# supra_redraw.net
KiCad netlist of a schematic drawn in EAGLE
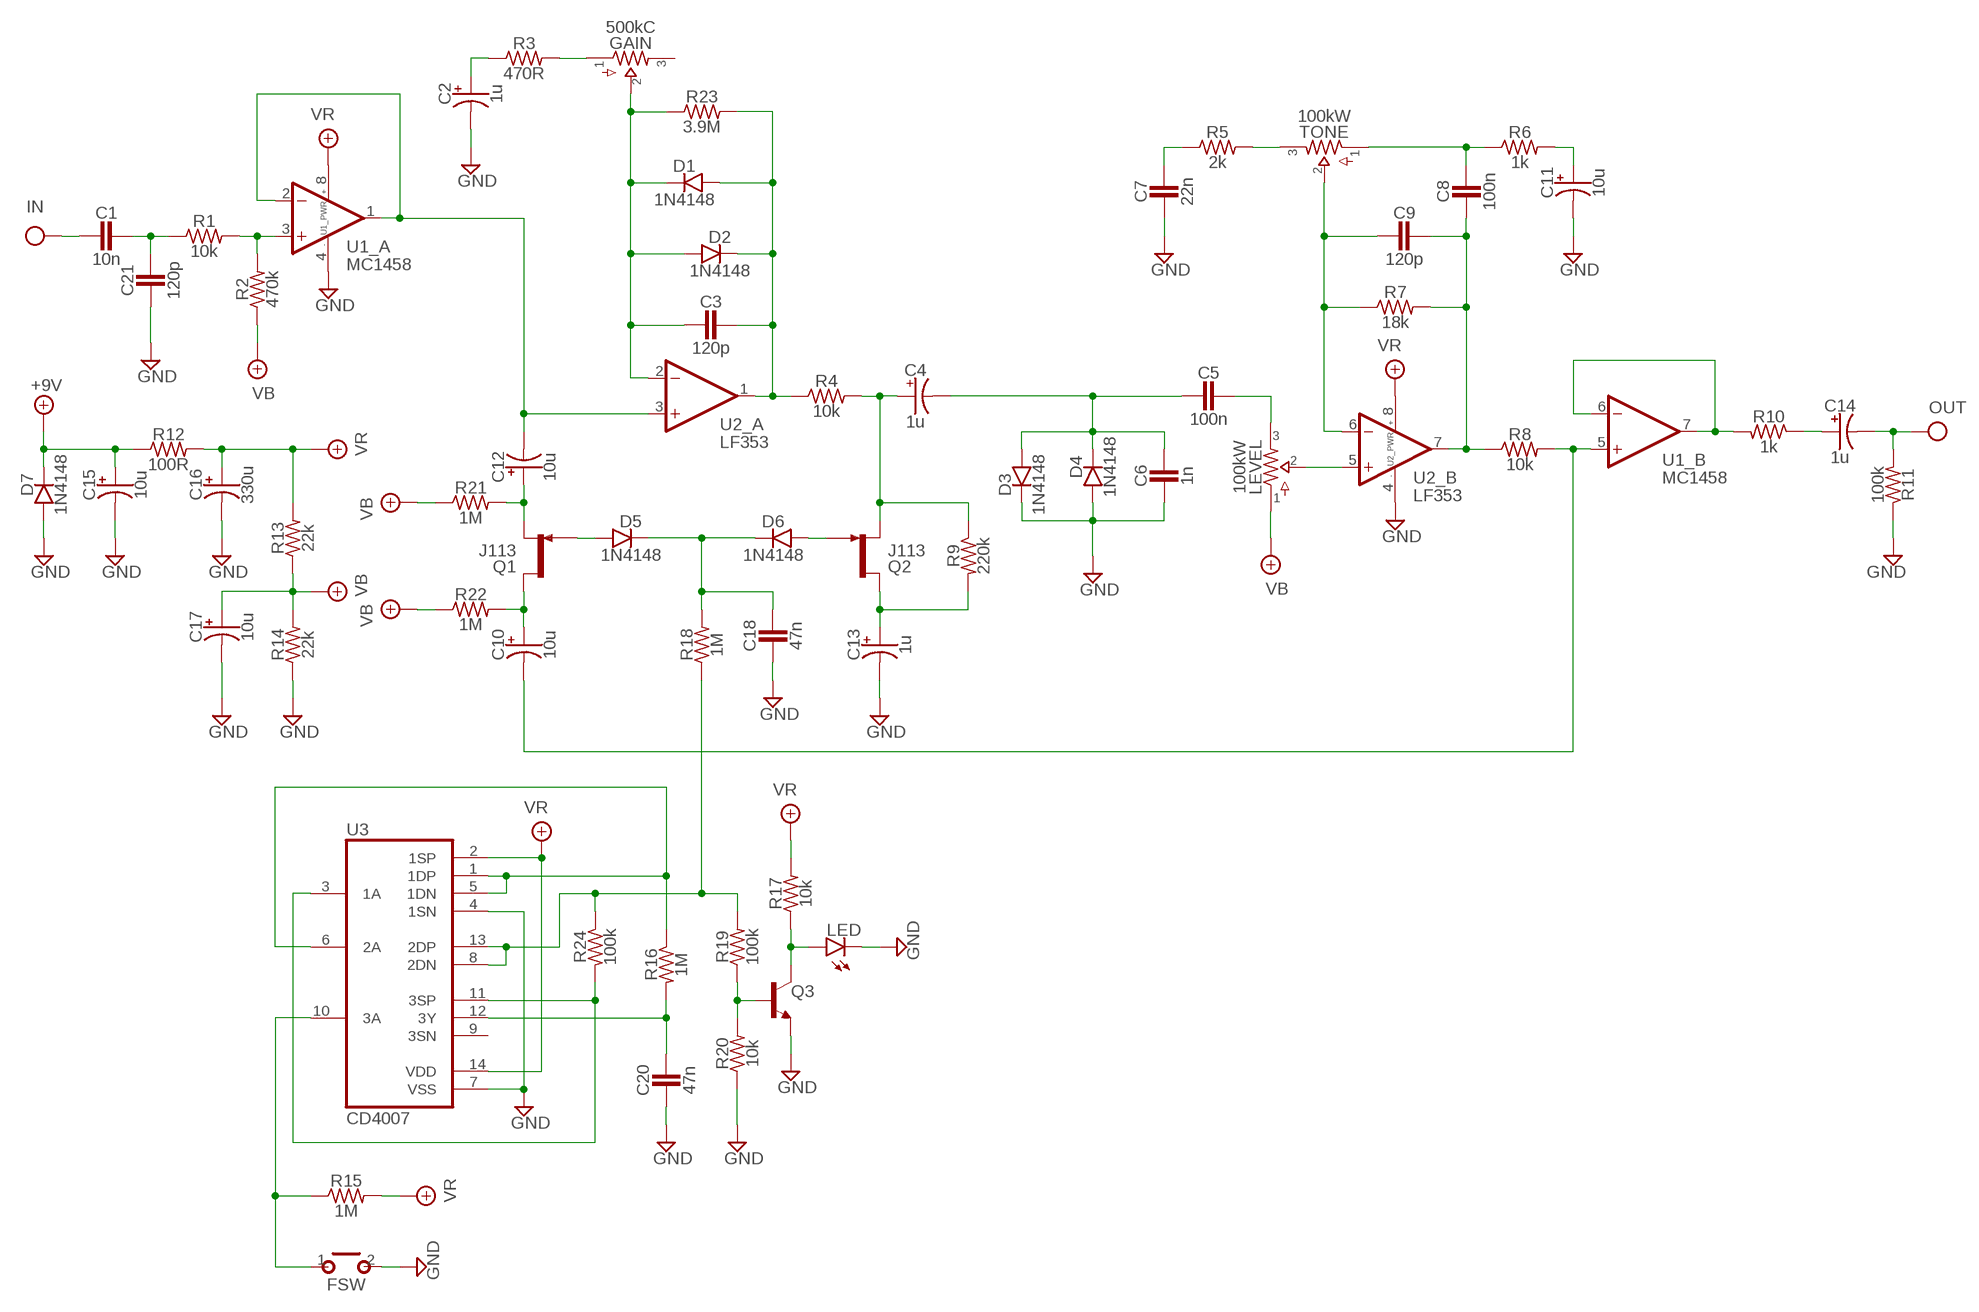
[diagram p0: schematic, sheet 1]

(export (version "E")
  (design (tool "Eeschema 10.0.6"))
  (components
    (comp (ref "C1")
      (value "10n")
      (footprint "eagle-import:BOX_SMALL")
      (libsource (lib "eagle-import") (part "CER/FILMBOX.1"))
    )
    (comp (ref "C2")
      (value "1u")
      (footprint "eagle-import:050_020")
      (libsource (lib "eagle-import") (part "0500"))
    )
    (comp (ref "C3")
      (value "120p")
      (footprint "eagle-import:BOX_SMALL")
      (libsource (lib "eagle-import") (part "CER/FILMBOX.1"))
    )
    (comp (ref "C4")
      (value "1u")
      (footprint "eagle-import:050_020")
      (libsource (lib "eagle-import") (part "0500"))
    )
    (comp (ref "C5")
      (value "100n")
      (footprint "eagle-import:BOX_SMALL")
      (libsource (lib "eagle-import") (part "CER/FILMBOX.1"))
    )
    (comp (ref "C6")
      (value "1n")
      (footprint "eagle-import:BOX_SMALL")
      (libsource (lib "eagle-import") (part "CER/FILMBOX.1"))
    )
    (comp (ref "C7")
      (value "22n")
      (footprint "eagle-import:BOX_SMALL")
      (libsource (lib "eagle-import") (part "CER/FILMBOX.1"))
    )
    (comp (ref "C8")
      (value "100n")
      (footprint "eagle-import:BOX_SMALL")
      (libsource (lib "eagle-import") (part "CER/FILMBOX.1"))
    )
    (comp (ref "C9")
      (value "120p")
      (footprint "eagle-import:BOX_SMALL")
      (libsource (lib "eagle-import") (part "CER/FILMBOX.1"))
    )
    (comp (ref "C10")
      (value "10u")
      (footprint "eagle-import:050_020")
      (libsource (lib "eagle-import") (part "0500"))
    )
    (comp (ref "C11")
      (value "10u")
      (footprint "eagle-import:050_020")
      (libsource (lib "eagle-import") (part "0500"))
    )
    (comp (ref "C12")
      (value "10u")
      (footprint "eagle-import:050_020")
      (libsource (lib "eagle-import") (part "0500"))
    )
    (comp (ref "C13")
      (value "1u")
      (footprint "eagle-import:050_020")
      (libsource (lib "eagle-import") (part "0500"))
    )
    (comp (ref "C14")
      (value "1u")
      (footprint "eagle-import:050_020")
      (libsource (lib "eagle-import") (part "0500"))
    )
    (comp (ref "C15")
      (value "10u")
      (footprint "eagle-import:050_020")
      (libsource (lib "eagle-import") (part "0500"))
    )
    (comp (ref "C16")
      (value "330u")
      (footprint "eagle-import:050_020")
      (libsource (lib "eagle-import") (part "0500"))
    )
    (comp (ref "C17")
      (value "10u")
      (footprint "eagle-import:050_020")
      (libsource (lib "eagle-import") (part "0500"))
    )
    (comp (ref "C18")
      (value "47n")
      (footprint "eagle-import:BOX_SMALL")
      (libsource (lib "eagle-import") (part "CER/FILMBOX.1"))
    )
    (comp (ref "C20")
      (value "47n")
      (footprint "eagle-import:BOX_SMALL")
      (libsource (lib "eagle-import") (part "CER/FILMBOX.1"))
    )
    (comp (ref "C21")
      (value "120p")
      (footprint "eagle-import:BOX_SMALL")
      (libsource (lib "eagle-import") (part "CER/FILMBOX.1"))
    )
    (comp (ref "D1")
      (value "1N4148")
      (footprint "eagle-import:DO35-2")
      (libsource (lib "eagle-import") (part "DO35.2"))
    )
    (comp (ref "D2")
      (value "1N4148")
      (footprint "eagle-import:DO35-2")
      (libsource (lib "eagle-import") (part "DO35.2"))
    )
    (comp (ref "D3")
      (value "1N4148")
      (footprint "eagle-import:DO35-2")
      (libsource (lib "eagle-import") (part "DO35.2"))
    )
    (comp (ref "D4")
      (value "1N4148")
      (footprint "eagle-import:DO35-2")
      (libsource (lib "eagle-import") (part "DO35.2"))
    )
    (comp (ref "D5")
      (value "1N4148")
      (footprint "eagle-import:DO35-2")
      (libsource (lib "eagle-import") (part "DO35.2"))
    )
    (comp (ref "D6")
      (value "1N4148")
      (footprint "eagle-import:DO35-2")
      (libsource (lib "eagle-import") (part "DO35.2"))
    )
    (comp (ref "D7")
      (value "1N4148")
      (footprint "eagle-import:DO35-2")
      (libsource (lib "eagle-import") (part "DO35.2"))
    )
    (comp (ref "FSW")
      (value "MOMENTARY")
      (footprint "eagle-import:SPST")
      (libsource (lib "eagle-import") (part "MOMENTARY"))
    )
    (comp (ref "GAIN")
      (value "500kC")
      (footprint "eagle-import:16MM")
      (libsource (lib "eagle-import") (part "POTS16MM"))
    )
    (comp (ref "LED")
      (value "LED")
      (footprint "eagle-import:3MM_D")
      (libsource (lib "eagle-import") (part "LED"))
    )
    (comp (ref "LEVEL")
      (value "100kW")
      (footprint "eagle-import:16MM")
      (libsource (lib "eagle-import") (part "POTS16MM"))
    )
    (comp (ref "Q1")
      (value "J113")
      (footprint "eagle-import:TO92-")
      (libsource (lib "eagle-import") (part "2N5457"))
    )
    (comp (ref "Q2")
      (value "J113")
      (footprint "eagle-import:TO92-")
      (libsource (lib "eagle-import") (part "2N5457"))
    )
    (comp (ref "Q3")
      (value "2N3904")
      (footprint "eagle-import:TO92-")
      (libsource (lib "eagle-import") (part "2N3904"))
    )
    (comp (ref "R1")
      (value "10k")
      (footprint "eagle-import:R0207_3")
      (libsource (lib "eagle-import") (part "R_.3B"))
    )
    (comp (ref "R2")
      (value "470k")
      (footprint "eagle-import:R0207_3")
      (libsource (lib "eagle-import") (part "R_.3B"))
    )
    (comp (ref "R3")
      (value "470R")
      (footprint "eagle-import:R0207_3")
      (libsource (lib "eagle-import") (part "R_.3B"))
    )
    (comp (ref "R4")
      (value "10k")
      (footprint "eagle-import:R0207_3")
      (libsource (lib "eagle-import") (part "R_.3B"))
    )
    (comp (ref "R5")
      (value "2k")
      (footprint "eagle-import:R0207_3")
      (libsource (lib "eagle-import") (part "R_.3B"))
    )
    (comp (ref "R6")
      (value "1k")
      (footprint "eagle-import:R0207_3")
      (libsource (lib "eagle-import") (part "R_.3B"))
    )
    (comp (ref "R7")
      (value "18k")
      (footprint "eagle-import:R0207_3")
      (libsource (lib "eagle-import") (part "R_.3B"))
    )
    (comp (ref "R8")
      (value "10k")
      (footprint "eagle-import:R0207_3")
      (libsource (lib "eagle-import") (part "R_.3B"))
    )
    (comp (ref "R9")
      (value "220k")
      (footprint "eagle-import:R0207_3")
      (libsource (lib "eagle-import") (part "R_.3B"))
    )
    (comp (ref "R10")
      (value "1k")
      (footprint "eagle-import:R0207_3")
      (libsource (lib "eagle-import") (part "R_.3B"))
    )
    (comp (ref "R11")
      (value "100k")
      (footprint "eagle-import:R0207_3")
      (libsource (lib "eagle-import") (part "R_.3B"))
    )
    (comp (ref "R12")
      (value "100R")
      (footprint "eagle-import:R0207_3")
      (libsource (lib "eagle-import") (part "R_.3B"))
    )
    (comp (ref "R13")
      (value "22k")
      (footprint "eagle-import:R0207_3")
      (libsource (lib "eagle-import") (part "R_.3B"))
    )
    (comp (ref "R14")
      (value "22k")
      (footprint "eagle-import:R0207_3")
      (libsource (lib "eagle-import") (part "R_.3B"))
    )
    (comp (ref "R15")
      (value "1M")
      (footprint "eagle-import:R0207_3")
      (libsource (lib "eagle-import") (part "R_.3B"))
    )
    (comp (ref "R16")
      (value "1M")
      (footprint "eagle-import:R0207_3")
      (libsource (lib "eagle-import") (part "R_.3B"))
    )
    (comp (ref "R17")
      (value "10k")
      (footprint "eagle-import:R0207_3")
      (libsource (lib "eagle-import") (part "R_.3B"))
    )
    (comp (ref "R18")
      (value "1M")
      (footprint "eagle-import:R0207_3")
      (libsource (lib "eagle-import") (part "R_.3B"))
    )
    (comp (ref "R19")
      (value "100k")
      (footprint "eagle-import:R0207_3")
      (libsource (lib "eagle-import") (part "R_.3B"))
    )
    (comp (ref "R20")
      (value "10k")
      (footprint "eagle-import:R0207_3")
      (libsource (lib "eagle-import") (part "R_.3B"))
    )
    (comp (ref "R21")
      (value "1M")
      (footprint "eagle-import:R0207_3")
      (libsource (lib "eagle-import") (part "R_.3B"))
    )
    (comp (ref "R22")
      (value "1M")
      (footprint "eagle-import:R0207_3")
      (libsource (lib "eagle-import") (part "R_.3B"))
    )
    (comp (ref "R23")
      (value "3.9M")
      (footprint "eagle-import:R0207_3")
      (libsource (lib "eagle-import") (part "R_.3B"))
    )
    (comp (ref "R24")
      (value "100k")
      (footprint "eagle-import:R0207_3")
      (libsource (lib "eagle-import") (part "R_.3B"))
    )
    (comp (ref "TONE")
      (value "100kW")
      (footprint "eagle-import:16MM")
      (libsource (lib "eagle-import") (part "POTS16MM"))
    )
    (comp (ref "U1")
      (value "MC1458")
      (footprint "eagle-import:DIL0")
      (libsource (lib "eagle-import") (part "DUALTH"))
    )
    (comp (ref "U2")
      (value "LF353")
      (footprint "eagle-import:DIL0")
      (libsource (lib "eagle-import") (part "DUALTH"))
    )
    (comp (ref "U3")
      (value "CD4007")
      (footprint "eagle-import:DIL14")
      (libsource (lib "eagle-import") (part "4007N"))
    )
  )
  (nets
    (net (code "1") (name "+9V") (class "Default")
      (node (ref "C15") (pin "+") (pinfunction "+_+") (pintype "passive"))
      (node (ref "D7") (pin "C") (pinfunction "C_C") (pintype "passive"))
      (node (ref "R12") (pin "1") (pinfunction "1_1") (pintype "passive"))
    )
    (net (code "2") (name "GND") (class "Default")
      (node (ref "C11") (pin "-") (pinfunction "-_-") (pintype "passive"))
      (node (ref "C13") (pin "-") (pinfunction "-_-") (pintype "passive"))
      (node (ref "C15") (pin "-") (pinfunction "-_-") (pintype "passive"))
      (node (ref "C16") (pin "-") (pinfunction "-_-") (pintype "passive"))
      (node (ref "C17") (pin "-") (pinfunction "-_-") (pintype "passive"))
      (node (ref "C18") (pin "2") (pinfunction "2_2") (pintype "passive"))
      (node (ref "C2") (pin "-") (pinfunction "-_-") (pintype "passive"))
      (node (ref "C20") (pin "2") (pinfunction "2_2") (pintype "passive"))
      (node (ref "C21") (pin "2") (pinfunction "2_2") (pintype "passive"))
      (node (ref "C6") (pin "2") (pinfunction "2_2") (pintype "passive"))
      (node (ref "C7") (pin "2") (pinfunction "2_2") (pintype "passive"))
      (node (ref "D3") (pin "C") (pinfunction "C_C") (pintype "passive"))
      (node (ref "D4") (pin "A") (pinfunction "A_A") (pintype "passive"))
      (node (ref "D7") (pin "A") (pinfunction "A_A") (pintype "passive"))
      (node (ref "FSW") (pin "2") (pinfunction "S_2") (pintype "passive"))
      (node (ref "LED") (pin "P$1") (pinfunction "C_P$1") (pintype "passive"))
      (node (ref "Q3") (pin "3") (pinfunction "E_3") (pintype "passive"))
      (node (ref "R11") (pin "1") (pinfunction "1_1") (pintype "passive"))
      (node (ref "R14") (pin "1") (pinfunction "1_1") (pintype "passive"))
      (node (ref "R20") (pin "1") (pinfunction "1_1") (pintype "passive"))
      (node (ref "U1") (pin "4") (pinfunction "V-_4") (pintype "power_in"))
      (node (ref "U2") (pin "4") (pinfunction "V-_4") (pintype "power_in"))
      (node (ref "U3") (pin "4") (pinfunction "1SN_4") (pintype "open_collector"))
      (node (ref "U3") (pin "7") (pinfunction "VSS_7") (pintype "input"))
    )
    (net (code "3") (name "IN") (class "Default")
      (node (ref "C1") (pin "2") (pinfunction "2_2") (pintype "passive"))
    )
    (net (code "4") (name "Net-(C1-Pad1)") (class "Default")
      (node (ref "C1") (pin "1") (pinfunction "1_1") (pintype "passive"))
      (node (ref "C21") (pin "1") (pinfunction "1_1") (pintype "passive"))
      (node (ref "R1") (pin "1") (pinfunction "1_1") (pintype "passive"))
    )
    (net (code "5") (name "Net-(C2-Pad+)") (class "Default")
      (node (ref "C2") (pin "+") (pinfunction "+_+") (pintype "passive"))
      (node (ref "R3") (pin "1") (pinfunction "1_1") (pintype "passive"))
    )
    (net (code "6") (name "Net-(C4-Pad-)") (class "Default")
      (node (ref "C4") (pin "-") (pinfunction "-_-") (pintype "passive"))
      (node (ref "C5") (pin "2") (pinfunction "2_2") (pintype "passive"))
      (node (ref "C6") (pin "1") (pinfunction "1_1") (pintype "passive"))
      (node (ref "D3") (pin "A") (pinfunction "A_A") (pintype "passive"))
      (node (ref "D4") (pin "C") (pinfunction "C_C") (pintype "passive"))
    )
    (net (code "7") (name "Net-(C5-Pad1)") (class "Default")
      (node (ref "C5") (pin "1") (pinfunction "1_1") (pintype "passive"))
      (node (ref "LEVEL") (pin "3") (pinfunction "3_3") (pintype "passive"))
    )
    (net (code "8") (name "Net-(C7-Pad1)") (class "Default")
      (node (ref "C7") (pin "1") (pinfunction "1_1") (pintype "passive"))
      (node (ref "R5") (pin "1") (pinfunction "1_1") (pintype "passive"))
    )
    (net (code "9") (name "Net-(C8-Pad1)") (class "Default")
      (node (ref "C8") (pin "1") (pinfunction "1_1") (pintype "passive"))
      (node (ref "R6") (pin "1") (pinfunction "1_1") (pintype "passive"))
      (node (ref "TONE") (pin "1") (pinfunction "1_1") (pintype "passive"))
    )
    (net (code "10") (name "Net-(C11-Pad+)") (class "Default")
      (node (ref "C11") (pin "+") (pinfunction "+_+") (pintype "passive"))
      (node (ref "R6") (pin "2") (pinfunction "2_2") (pintype "passive"))
    )
    (net (code "11") (name "Net-(C14-Pad+)") (class "Default")
      (node (ref "C14") (pin "+") (pinfunction "+_+") (pintype "passive"))
      (node (ref "R10") (pin "1") (pinfunction "1_1") (pintype "passive"))
    )
    (net (code "12") (name "Net-(C18-Pad1)") (class "Default")
      (node (ref "C18") (pin "1") (pinfunction "1_1") (pintype "passive"))
      (node (ref "D5") (pin "C") (pinfunction "C_C") (pintype "passive"))
      (node (ref "D6") (pin "C") (pinfunction "C_C") (pintype "passive"))
      (node (ref "R18") (pin "2") (pinfunction "2_2") (pintype "passive"))
    )
    (net (code "13") (name "Net-(FSW-P)") (class "Default")
      (node (ref "FSW") (pin "1") (pinfunction "P_1") (pintype "passive"))
      (node (ref "R15") (pin "1") (pinfunction "1_1") (pintype "passive"))
      (node (ref "U3") (pin "10") (pinfunction "3A_10") (pintype "input"))
    )
    (net (code "14") (name "Net-(GAIN-Pad1)") (class "Default")
      (node (ref "GAIN") (pin "1") (pinfunction "1_1") (pintype "passive"))
      (node (ref "R3") (pin "2") (pinfunction "2_2") (pintype "passive"))
    )
    (net (code "15") (name "Net-(LED-A)") (class "Default")
      (node (ref "LED") (pin "ANODE") (pinfunction "A_ANODE") (pintype "passive"))
      (node (ref "Q3") (pin "1") (pinfunction "C_1") (pintype "passive"))
      (node (ref "R17") (pin "1") (pinfunction "1_1") (pintype "passive"))
    )
    (net (code "16") (name "Net-(Q1-D)") (class "Default")
      (node (ref "C10") (pin "+") (pinfunction "+_+") (pintype "passive"))
      (node (ref "Q1") (pin "3") (pinfunction "D_3") (pintype "passive"))
      (node (ref "R22") (pin "2") (pinfunction "2_2") (pintype "passive"))
    )
    (net (code "17") (name "Net-(Q1-G)") (class "Default")
      (node (ref "D5") (pin "A") (pinfunction "A_A") (pintype "passive"))
      (node (ref "Q1") (pin "1") (pinfunction "G_1") (pintype "passive"))
    )
    (net (code "18") (name "Net-(Q1-S)") (class "Default")
      (node (ref "C12") (pin "+") (pinfunction "+_+") (pintype "passive"))
      (node (ref "Q1") (pin "2") (pinfunction "S_2") (pintype "passive"))
      (node (ref "R21") (pin "2") (pinfunction "2_2") (pintype "passive"))
    )
    (net (code "19") (name "Net-(Q2-D)") (class "Default")
      (node (ref "C13") (pin "+") (pinfunction "+_+") (pintype "passive"))
      (node (ref "Q2") (pin "3") (pinfunction "D_3") (pintype "passive"))
      (node (ref "R9") (pin "2") (pinfunction "2_2") (pintype "passive"))
    )
    (net (code "20") (name "Net-(Q2-G)") (class "Default")
      (node (ref "D6") (pin "A") (pinfunction "A_A") (pintype "passive"))
      (node (ref "Q2") (pin "1") (pinfunction "G_1") (pintype "passive"))
    )
    (net (code "21") (name "Net-(Q2-S)") (class "Default")
      (node (ref "C4") (pin "+") (pinfunction "+_+") (pintype "passive"))
      (node (ref "Q2") (pin "2") (pinfunction "S_2") (pintype "passive"))
      (node (ref "R4") (pin "2") (pinfunction "2_2") (pintype "passive"))
      (node (ref "R9") (pin "1") (pinfunction "1_1") (pintype "passive"))
    )
    (net (code "22") (name "Net-(Q3-B)") (class "Default")
      (node (ref "Q3") (pin "2") (pinfunction "B_2") (pintype "passive"))
      (node (ref "R19") (pin "1") (pinfunction "1_1") (pintype "passive"))
      (node (ref "R20") (pin "2") (pinfunction "2_2") (pintype "passive"))
    )
    (net (code "23") (name "Net-(R5-Pad2)") (class "Default")
      (node (ref "R5") (pin "2") (pinfunction "2_2") (pintype "passive"))
      (node (ref "TONE") (pin "3") (pinfunction "3_3") (pintype "passive"))
    )
    (net (code "24") (name "Net-(U1A-+IN)") (class "Default")
      (node (ref "R1") (pin "2") (pinfunction "2_2") (pintype "passive"))
      (node (ref "R2") (pin "2") (pinfunction "2_2") (pintype "passive"))
      (node (ref "U1") (pin "3") (pinfunction "+IN_3") (pintype "input"))
    )
    (net (code "25") (name "Net-(U1A--IN)") (class "Default")
      (node (ref "C12") (pin "-") (pinfunction "-_-") (pintype "passive"))
      (node (ref "U1") (pin "1") (pinfunction "OUT_1") (pintype "output"))
      (node (ref "U1") (pin "2") (pinfunction "-IN_2") (pintype "input"))
      (node (ref "U2") (pin "3") (pinfunction "+IN_3") (pintype "input"))
    )
    (net (code "26") (name "Net-(U1B-+IN)") (class "Default")
      (node (ref "C10") (pin "-") (pinfunction "-_-") (pintype "passive"))
      (node (ref "R8") (pin "2") (pinfunction "2_2") (pintype "passive"))
      (node (ref "U1") (pin "5") (pinfunction "+IN_5") (pintype "input"))
    )
    (net (code "27") (name "Net-(U1B--IN)") (class "Default")
      (node (ref "R10") (pin "2") (pinfunction "2_2") (pintype "passive"))
      (node (ref "U1") (pin "6") (pinfunction "-IN_6") (pintype "input"))
      (node (ref "U1") (pin "7") (pinfunction "OUT_7") (pintype "output"))
    )
    (net (code "28") (name "Net-(U2A--IN)") (class "Default")
      (node (ref "C3") (pin "2") (pinfunction "2_2") (pintype "passive"))
      (node (ref "D1") (pin "C") (pinfunction "C_C") (pintype "passive"))
      (node (ref "D2") (pin "A") (pinfunction "A_A") (pintype "passive"))
      (node (ref "GAIN") (pin "2") (pinfunction "2_2") (pintype "passive"))
      (node (ref "R23") (pin "1") (pinfunction "1_1") (pintype "passive"))
      (node (ref "U2") (pin "2") (pinfunction "-IN_2") (pintype "input"))
    )
    (net (code "29") (name "Net-(U2A-OUT)") (class "Default")
      (node (ref "C3") (pin "1") (pinfunction "1_1") (pintype "passive"))
      (node (ref "D1") (pin "A") (pinfunction "A_A") (pintype "passive"))
      (node (ref "D2") (pin "C") (pinfunction "C_C") (pintype "passive"))
      (node (ref "R23") (pin "2") (pinfunction "2_2") (pintype "passive"))
      (node (ref "R4") (pin "1") (pinfunction "1_1") (pintype "passive"))
      (node (ref "U2") (pin "1") (pinfunction "OUT_1") (pintype "output"))
    )
    (net (code "30") (name "Net-(U2B-+IN)") (class "Default")
      (node (ref "LEVEL") (pin "2") (pinfunction "2_2") (pintype "passive"))
      (node (ref "U2") (pin "5") (pinfunction "+IN_5") (pintype "input"))
    )
    (net (code "31") (name "Net-(U2B--IN)") (class "Default")
      (node (ref "C9") (pin "2") (pinfunction "2_2") (pintype "passive"))
      (node (ref "R7") (pin "1") (pinfunction "1_1") (pintype "passive"))
      (node (ref "TONE") (pin "2") (pinfunction "2_2") (pintype "passive"))
      (node (ref "U2") (pin "6") (pinfunction "-IN_6") (pintype "input"))
    )
    (net (code "32") (name "Net-(U2B-OUT)") (class "Default")
      (node (ref "C8") (pin "2") (pinfunction "2_2") (pintype "passive"))
      (node (ref "C9") (pin "1") (pinfunction "1_1") (pintype "passive"))
      (node (ref "R7") (pin "2") (pinfunction "2_2") (pintype "passive"))
      (node (ref "R8") (pin "1") (pinfunction "1_1") (pintype "passive"))
      (node (ref "U2") (pin "7") (pinfunction "OUT_7") (pintype "output"))
    )
    (net (code "33") (name "Net-(U3-1A)") (class "Default")
      (node (ref "R24") (pin "2") (pinfunction "2_2") (pintype "passive"))
      (node (ref "U3") (pin "11") (pinfunction "3SP_11") (pintype "bidirectional"))
      (node (ref "U3") (pin "3") (pinfunction "1A_3") (pintype "input"))
    )
    (net (code "34") (name "Net-(U3-1DN)") (class "Default")
      (node (ref "R16") (pin "1") (pinfunction "1_1") (pintype "passive"))
      (node (ref "U3") (pin "1") (pinfunction "1DP_1") (pintype "open_collector"))
      (node (ref "U3") (pin "5") (pinfunction "1DN_5") (pintype "open_collector"))
      (node (ref "U3") (pin "6") (pinfunction "2A_6") (pintype "input"))
    )
    (net (code "35") (name "Net-(U3-2DN)") (class "Default")
      (node (ref "R18") (pin "1") (pinfunction "1_1") (pintype "passive"))
      (node (ref "R19") (pin "2") (pinfunction "2_2") (pintype "passive"))
      (node (ref "R24") (pin "1") (pinfunction "1_1") (pintype "passive"))
      (node (ref "U3") (pin "13") (pinfunction "2DP_13") (pintype "bidirectional"))
      (node (ref "U3") (pin "8") (pinfunction "2DN_8") (pintype "bidirectional"))
    )
    (net (code "36") (name "Net-(U3-3Y)") (class "Default")
      (node (ref "C20") (pin "1") (pinfunction "1_1") (pintype "passive"))
      (node (ref "R16") (pin "2") (pinfunction "2_2") (pintype "passive"))
      (node (ref "U3") (pin "12") (pinfunction "3Y_12") (pintype "bidirectional"))
    )
    (net (code "37") (name "OUT") (class "Default")
      (node (ref "C14") (pin "-") (pinfunction "-_-") (pintype "passive"))
      (node (ref "R11") (pin "2") (pinfunction "2_2") (pintype "passive"))
    )
    (net (code "38") (name "VB") (class "Default")
      (node (ref "C17") (pin "+") (pinfunction "+_+") (pintype "passive"))
      (node (ref "LEVEL") (pin "1") (pinfunction "1_1") (pintype "passive"))
      (node (ref "R13") (pin "1") (pinfunction "1_1") (pintype "passive"))
      (node (ref "R14") (pin "2") (pinfunction "2_2") (pintype "passive"))
      (node (ref "R2") (pin "1") (pinfunction "1_1") (pintype "passive"))
      (node (ref "R21") (pin "1") (pinfunction "1_1") (pintype "passive"))
      (node (ref "R22") (pin "1") (pinfunction "1_1") (pintype "passive"))
    )
    (net (code "39") (name "VR") (class "Default")
      (node (ref "C16") (pin "+") (pinfunction "+_+") (pintype "passive"))
      (node (ref "R12") (pin "2") (pinfunction "2_2") (pintype "passive"))
      (node (ref "R13") (pin "2") (pinfunction "2_2") (pintype "passive"))
      (node (ref "R15") (pin "2") (pinfunction "2_2") (pintype "passive"))
      (node (ref "R17") (pin "2") (pinfunction "2_2") (pintype "passive"))
      (node (ref "U1") (pin "8") (pinfunction "V+_8") (pintype "power_in"))
      (node (ref "U2") (pin "8") (pinfunction "V+_8") (pintype "power_in"))
      (node (ref "U3") (pin "14") (pinfunction "VDD_14") (pintype "input"))
      (node (ref "U3") (pin "2") (pinfunction "1SP_2") (pintype "open_collector"))
    )
    (net (code "40") (name "unconnected-(GAIN-Pad3)") (class "Default")
      (node (ref "GAIN") (pin "3") (pinfunction "3_3") (pintype "passive"))
    )
    (net (code "41") (name "unconnected-(U3-3SN-Pad9)") (class "Default")
      (node (ref "U3") (pin "9") (pinfunction "3SN_9") (pintype "bidirectional"))
    )
  )
)
